# Filter_Capacitors_-_FOTA_ICSP.net
KiCad netlist of a schematic drawn in Altium Designer
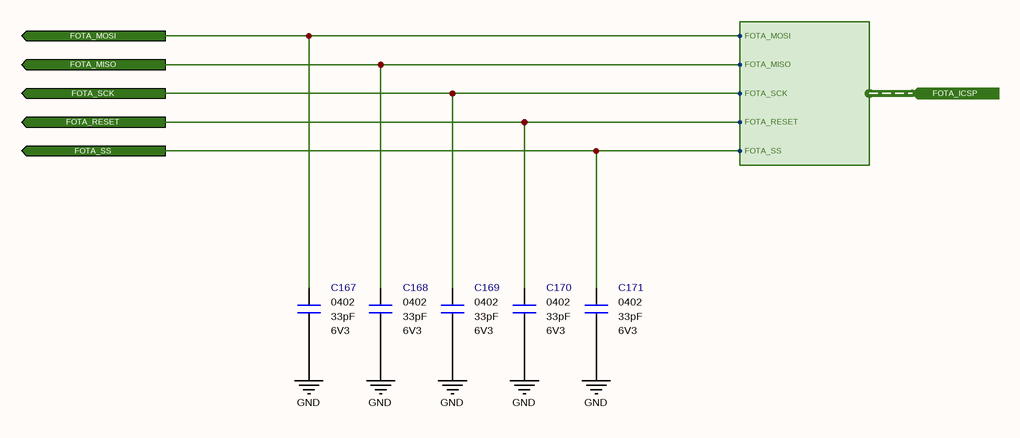
[diagram p0: Filter Capacitors - FOTA ICSP.SchDoc]

(export (version "E")
  (design (tool "Eeschema 10.0.6"))
  (components
    (comp (ref "C167")
      (value "33pF")
      (footprint "CAPACITOR_0402")
      (description "Capacitor - 33pF [0402] (Ceramic)")
      (fields
        (field (name "TOLERANCE") "10%")
        (field (name "CASE") "0402")
        (field (name "VOLTAGE") "6V3")
        (field (name "MANUFACTURER PART NUMBER") "C0402C330J9RACAUTO")
      )
      (libsource (lib "Ovoo_Library") (part "Capacitor - 33pF [0402-6V3]"))
    )
    (comp (ref "C168")
      (value "33pF")
      (footprint "CAPACITOR_0402")
      (description "Capacitor - 33pF [0402] (Ceramic)")
      (fields
        (field (name "TOLERANCE") "10%")
        (field (name "CASE") "0402")
        (field (name "VOLTAGE") "6V3")
        (field (name "MANUFACTURER PART NUMBER") "C0402C330J9RACAUTO")
      )
      (libsource (lib "Ovoo_Library") (part "Capacitor - 33pF [0402-6V3]"))
    )
    (comp (ref "C169")
      (value "33pF")
      (footprint "CAPACITOR_0402")
      (description "Capacitor - 33pF [0402] (Ceramic)")
      (fields
        (field (name "TOLERANCE") "10%")
        (field (name "CASE") "0402")
        (field (name "VOLTAGE") "6V3")
        (field (name "MANUFACTURER PART NUMBER") "C0402C330J9RACAUTO")
      )
      (libsource (lib "Ovoo_Library") (part "Capacitor - 33pF [0402-6V3]"))
    )
    (comp (ref "C170")
      (value "33pF")
      (footprint "CAPACITOR_0402")
      (description "Capacitor - 33pF [0402] (Ceramic)")
      (fields
        (field (name "TOLERANCE") "10%")
        (field (name "CASE") "0402")
        (field (name "VOLTAGE") "6V3")
        (field (name "MANUFACTURER PART NUMBER") "C0402C330J9RACAUTO")
      )
      (libsource (lib "Ovoo_Library") (part "Capacitor - 33pF [0402-6V3]"))
    )
    (comp (ref "C171")
      (value "33pF")
      (footprint "CAPACITOR_0402")
      (description "Capacitor - 33pF [0402] (Ceramic)")
      (fields
        (field (name "TOLERANCE") "10%")
        (field (name "CASE") "0402")
        (field (name "VOLTAGE") "6V3")
        (field (name "MANUFACTURER PART NUMBER") "C0402C330J9RACAUTO")
      )
      (libsource (lib "Ovoo_Library") (part "Capacitor - 33pF [0402-6V3]"))
    )
  )
  (nets
    (net (code "2") (name "/FOTA_MISO") (class "Default")
      (node (ref "C168") (pin "2") (pinfunction "2_2") (pintype "passive"))
    )
    (net (code "3") (name "/FOTA_MOSI") (class "Default")
      (node (ref "C167") (pin "2") (pinfunction "2_2") (pintype "passive"))
    )
    (net (code "4") (name "/FOTA_RESET") (class "Default")
      (node (ref "C170") (pin "2") (pinfunction "2_2") (pintype "passive"))
    )
    (net (code "5") (name "/FOTA_SCK") (class "Default")
      (node (ref "C169") (pin "2") (pinfunction "2_2") (pintype "passive"))
    )
    (net (code "6") (name "/FOTA_SS") (class "Default")
      (node (ref "C171") (pin "2") (pinfunction "2_2") (pintype "passive"))
    )
    (net (code "8") (name "GND") (class "Default")
      (node (ref "C167") (pin "1") (pinfunction "1_1") (pintype "passive"))
      (node (ref "C168") (pin "1") (pinfunction "1_1") (pintype "passive"))
      (node (ref "C169") (pin "1") (pinfunction "1_1") (pintype "passive"))
      (node (ref "C170") (pin "1") (pinfunction "1_1") (pintype "passive"))
      (node (ref "C171") (pin "1") (pinfunction "1_1") (pintype "passive"))
    )
  )
)
